# 8266_DIYIOT_Board_F_AS_V_G.net
KiCad netlist of a schematic drawn in EAGLE
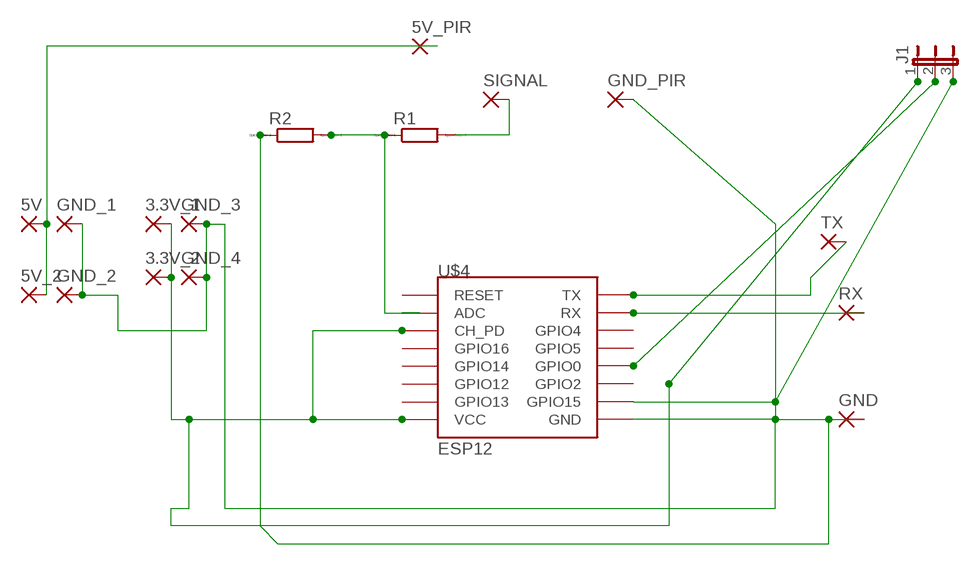
[diagram p0: schematic, sheet 1]

(export (version "E")
  (design (tool "Eeschema 10.0.6"))
  (components
    (comp (ref "3.3V_1")
      (value "2,15/1,0")
      (footprint "eagle-import:2,15_1,0")
      (libsource (lib "eagle-import") (part "2,15/1,0"))
    )
    (comp (ref "3.3V_2")
      (value "2,15/1,0")
      (footprint "eagle-import:2,15_1,0")
      (libsource (lib "eagle-import") (part "2,15/1,0"))
    )
    (comp (ref "5V")
      (value "2,15/1,0")
      (footprint "eagle-import:2,15_1,0")
      (libsource (lib "eagle-import") (part "2,15/1,0"))
    )
    (comp (ref "5V_2")
      (value "2,15/1,0")
      (footprint "eagle-import:2,15_1,0")
      (libsource (lib "eagle-import") (part "2,15/1,0"))
    )
    (comp (ref "5V_PIR")
      (value "2,15/1,0")
      (footprint "eagle-import:2,15_1,0")
      (libsource (lib "eagle-import") (part "2,15/1,0"))
    )
    (comp (ref "GND")
      (value "2,15/1,0")
      (footprint "eagle-import:2,15_1,0")
      (libsource (lib "eagle-import") (part "2,15/1,0"))
    )
    (comp (ref "GND_1")
      (value "2,15/1,0")
      (footprint "eagle-import:2,15_1,0")
      (libsource (lib "eagle-import") (part "2,15/1,0"))
    )
    (comp (ref "GND_2")
      (value "2,15/1,0")
      (footprint "eagle-import:2,15_1,0")
      (libsource (lib "eagle-import") (part "2,15/1,0"))
    )
    (comp (ref "GND_3")
      (value "2,15/1,0")
      (footprint "eagle-import:2,15_1,0")
      (libsource (lib "eagle-import") (part "2,15/1,0"))
    )
    (comp (ref "GND_4")
      (value "2,15/1,0")
      (footprint "eagle-import:2,15_1,0")
      (libsource (lib "eagle-import") (part "2,15/1,0"))
    )
    (comp (ref "GND_PIR")
      (value "2,15/1,0")
      (footprint "eagle-import:2,15_1,0")
      (libsource (lib "eagle-import") (part "2,15/1,0"))
    )
    (comp (ref "J1")
      (value "JP2E")
      (footprint "eagle-import:JP2")
      (libsource (lib "eagle-import") (part "JP2E"))
    )
    (comp (ref "R1")
      (value "R0204/7")
      (footprint "eagle-import:0204_7")
      (libsource (lib "eagle-import") (part "R0204/7"))
    )
    (comp (ref "R2")
      (value "R0204/7")
      (footprint "eagle-import:0204_7")
      (libsource (lib "eagle-import") (part "R0204/7"))
    )
    (comp (ref "RX")
      (value "2,15/1,0")
      (footprint "eagle-import:2,15_1,0")
      (libsource (lib "eagle-import") (part "2,15/1,0"))
    )
    (comp (ref "SIGNAL")
      (value "2,15/1,0")
      (footprint "eagle-import:2,15_1,0")
      (libsource (lib "eagle-import") (part "2,15/1,0"))
    )
    (comp (ref "TX")
      (value "2,15/1,0")
      (footprint "eagle-import:2,15_1,0")
      (libsource (lib "eagle-import") (part "2,15/1,0"))
    )
    (comp (ref "U$4")
      (value "ESP12")
      (footprint "eagle-import:ESP12")
      (libsource (lib "eagle-import") (part "ESP12"))
    )
  )
  (nets
    (net (code "1") (name "/5V") (class "Default")
      (node (ref "5V") (pin "1") (pinfunction "P_1") (pintype "passive"))
      (node (ref "5V_2") (pin "1") (pinfunction "P_1") (pintype "passive"))
      (node (ref "5V_PIR") (pin "1") (pinfunction "P_1") (pintype "passive"))
      (node (ref "GND") (pin "1") (pinfunction "P_1") (pintype "passive"))
      (node (ref "GND_1") (pin "1") (pinfunction "P_1") (pintype "passive"))
      (node (ref "GND_2") (pin "1") (pinfunction "P_1") (pintype "passive"))
      (node (ref "GND_3") (pin "1") (pinfunction "P_1") (pintype "passive"))
      (node (ref "GND_4") (pin "1") (pinfunction "P_1") (pintype "passive"))
      (node (ref "GND_PIR") (pin "1") (pinfunction "P_1") (pintype "passive"))
      (node (ref "J1") (pin "3") (pinfunction "3_3") (pintype "passive"))
      (node (ref "R2") (pin "1") (pinfunction "1_1") (pintype "passive"))
      (node (ref "U$4") (pin "GND") (pinfunction "GND_GND") (pintype "bidirectional"))
      (node (ref "U$4") (pin "GPIO15") (pinfunction "GPIO15_GPIO15") (pintype "bidirectional"))
    )
    (net (code "2") (name "Net-(3.3V_1-P)") (class "Default")
      (node (ref "3.3V_1") (pin "1") (pinfunction "P_1") (pintype "passive"))
      (node (ref "3.3V_2") (pin "1") (pinfunction "P_1") (pintype "passive"))
      (node (ref "J1") (pin "1") (pinfunction "1_1") (pintype "passive"))
      (node (ref "U$4") (pin "CH_PD") (pinfunction "CH_PD_CH_PD") (pintype "bidirectional"))
      (node (ref "U$4") (pin "VCC") (pinfunction "VCC_VCC") (pintype "bidirectional"))
    )
    (net (code "3") (name "Net-(J1-Pad2)") (class "Default")
      (node (ref "J1") (pin "2") (pinfunction "2_2") (pintype "passive"))
      (node (ref "U$4") (pin "GPIO0") (pinfunction "GPIO0_GPIO0") (pintype "bidirectional"))
    )
    (net (code "4") (name "Net-(R1-Pad1)") (class "Default")
      (node (ref "R1") (pin "1") (pinfunction "1_1") (pintype "passive"))
      (node (ref "R2") (pin "2") (pinfunction "2_2") (pintype "passive"))
      (node (ref "U$4") (pin "ADC") (pinfunction "ADC_ADC") (pintype "bidirectional"))
    )
    (net (code "5") (name "Net-(RX-P)") (class "Default")
      (node (ref "RX") (pin "1") (pinfunction "P_1") (pintype "passive"))
      (node (ref "U$4") (pin "RX") (pinfunction "RX_RX") (pintype "bidirectional"))
    )
    (net (code "6") (name "Net-(SIGNAL-P)") (class "Default")
      (node (ref "R1") (pin "2") (pinfunction "2_2") (pintype "passive"))
      (node (ref "SIGNAL") (pin "1") (pinfunction "P_1") (pintype "passive"))
    )
    (net (code "7") (name "Net-(TX-P)") (class "Default")
      (node (ref "TX") (pin "1") (pinfunction "P_1") (pintype "passive"))
      (node (ref "U$4") (pin "TX") (pinfunction "TX_TX") (pintype "bidirectional"))
    )
    (net (code "8") (name "unconnected-(U$4-PadGPIO2)") (class "Default")
      (node (ref "U$4") (pin "GPIO2") (pinfunction "GPIO2_GPIO2") (pintype "bidirectional"))
    )
    (net (code "9") (name "unconnected-(U$4-PadGPIO4)") (class "Default")
      (node (ref "U$4") (pin "GPIO4") (pinfunction "GPIO4_GPIO4") (pintype "bidirectional"))
    )
    (net (code "10") (name "unconnected-(U$4-PadGPIO5)") (class "Default")
      (node (ref "U$4") (pin "GPIO5") (pinfunction "GPIO5_GPIO5") (pintype "bidirectional"))
    )
    (net (code "11") (name "unconnected-(U$4-PadGPIO12)") (class "Default")
      (node (ref "U$4") (pin "GPIO12") (pinfunction "GPIO12_GPIO12") (pintype "bidirectional"))
    )
    (net (code "12") (name "unconnected-(U$4-PadGPIO13)") (class "Default")
      (node (ref "U$4") (pin "GPIO13") (pinfunction "GPIO13_GPIO13") (pintype "bidirectional"))
    )
    (net (code "13") (name "unconnected-(U$4-PadGPIO14)") (class "Default")
      (node (ref "U$4") (pin "GPIO14") (pinfunction "GPIO14_GPIO14") (pintype "bidirectional"))
    )
    (net (code "14") (name "unconnected-(U$4-PadGPIO16)") (class "Default")
      (node (ref "U$4") (pin "GPIO16") (pinfunction "GPIO16_GPIO16") (pintype "bidirectional"))
    )
    (net (code "15") (name "unconnected-(U$4-PadRESET)") (class "Default")
      (node (ref "U$4") (pin "RESET") (pinfunction "RESET_RESET") (pintype "bidirectional"))
    )
  )
)
